# Power.net
KiCad netlist of a schematic drawn in Altium Designer
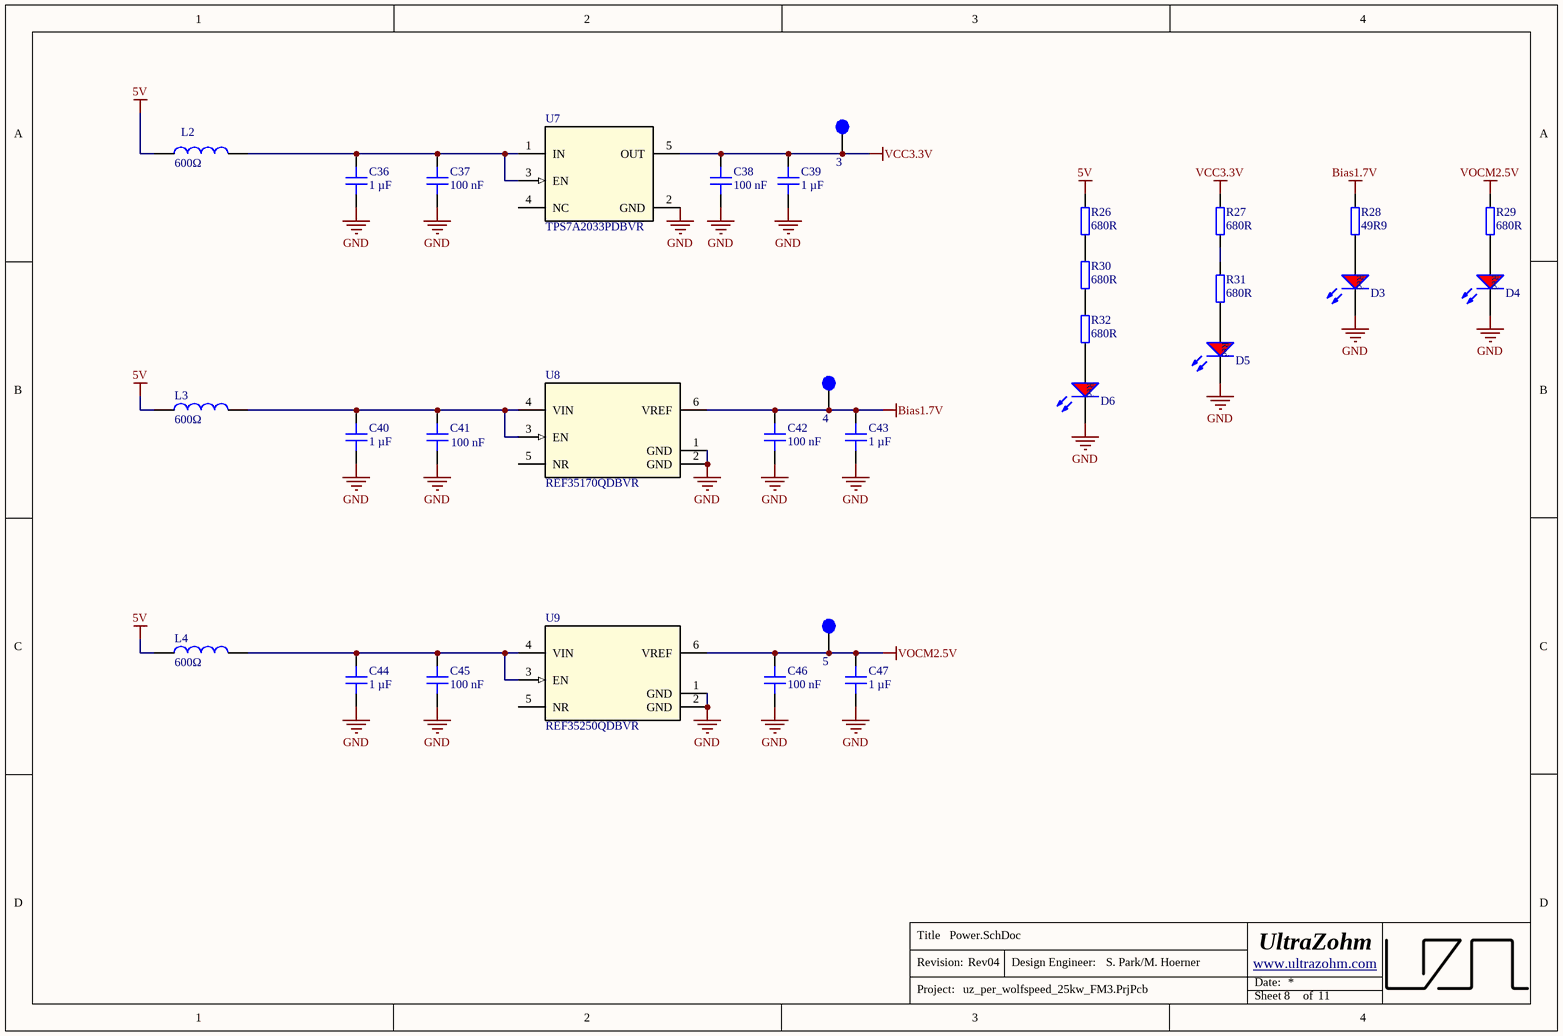
[diagram p0: Power.SchDoc]

(export (version "E")
  (design (tool "Eeschema 10.0.6"))
  (components
    (comp (ref "3")
      (value "Testpoint 1mm")
      (footprint "TP_1mm")
      (fields (field (name "CREATED") "2018_06_25_AGeiger"))
      (libsource (lib "UZOhm_Optical") (part "TP_1mm"))
    )
    (comp (ref "4")
      (value "Testpoint 1mm")
      (footprint "TP_1mm")
      (fields (field (name "CREATED") "2018_06_25_AGeiger"))
      (libsource (lib "UZOhm_Optical") (part "TP_1mm"))
    )
    (comp (ref "5")
      (value "Testpoint 1mm")
      (footprint "TP_1mm")
      (fields (field (name "CREATED") "2018_06_25_AGeiger"))
      (libsource (lib "UZOhm_Optical") (part "TP_1mm"))
    )
    (comp (ref "C36")
      (value "1 µF")
      (footprint "C_0603")
      (description "Capacitor 0603, 25 VDC, 1 µF, X7R")
      (fields
        (field (name "MANUFACTURER PART NUMBER") "C0603C105K3RAC7411")
        (field (name "MANUFACTURER") "KEMET")
        (field (name "CREATED FROM") "MGremer")
      )
      (libsource (lib "user") (part "Capacitor"))
    )
    (comp (ref "C37")
      (value "100 nF")
      (footprint "C_0603")
      (description "Capacitor 0603, 50 VDC, 100nF, X7R")
      (fields
        (field (name "MANUFACTURER PART NUMBER") "C0603C104K5RAC3121")
        (field (name "MANUFACTURER") "KEMET")
        (field (name "CREATED FROM") "DHufnagel")
      )
      (libsource (lib "user") (part "Capacitor"))
    )
    (comp (ref "C38")
      (value "100 nF")
      (footprint "C_0603")
      (description "Capacitor 0603, 50 VDC, 100nF, X7R")
      (fields
        (field (name "MANUFACTURER PART NUMBER") "C0603C104K5RAC3121")
        (field (name "MANUFACTURER") "KEMET")
        (field (name "CREATED FROM") "DHufnagel")
      )
      (libsource (lib "user") (part "Capacitor"))
    )
    (comp (ref "C39")
      (value "1 µF")
      (footprint "C_0603")
      (description "Capacitor 0603, 25 VDC, 1 µF, X7R")
      (fields
        (field (name "MANUFACTURER PART NUMBER") "C0603C105K3RAC7411")
        (field (name "MANUFACTURER") "KEMET")
        (field (name "CREATED FROM") "MGremer")
      )
      (libsource (lib "user") (part "Capacitor"))
    )
    (comp (ref "C40")
      (value "1 µF")
      (footprint "C_0603")
      (description "Capacitor 0603, 25 VDC, 1 µF, X7R")
      (fields
        (field (name "MANUFACTURER PART NUMBER") "C0603C105K3RAC7411")
        (field (name "MANUFACTURER") "KEMET")
        (field (name "CREATED FROM") "MGremer")
      )
      (libsource (lib "user") (part "Capacitor"))
    )
    (comp (ref "C41")
      (value "100 nF")
      (footprint "C_0603")
      (description "Capacitor 0603, 50 VDC, 100nF, X7R")
      (fields
        (field (name "MANUFACTURER PART NUMBER") "C0603C104K5RAC3121")
        (field (name "MANUFACTURER") "KEMET")
        (field (name "CREATED FROM") "DHufnagel")
      )
      (libsource (lib "user") (part "Capacitor"))
    )
    (comp (ref "C42")
      (value "100 nF")
      (footprint "C_0603")
      (description "Capacitor 0603, 50 VDC, 100nF, X7R")
      (fields
        (field (name "MANUFACTURER PART NUMBER") "C0603C104K5RAC3121")
        (field (name "MANUFACTURER") "KEMET")
        (field (name "CREATED FROM") "DHufnagel")
      )
      (libsource (lib "user") (part "Capacitor"))
    )
    (comp (ref "C43")
      (value "1 µF")
      (footprint "C_0603")
      (description "Capacitor 0603, 25 VDC, 1 µF, X7R")
      (fields
        (field (name "MANUFACTURER PART NUMBER") "C0603C105K3RAC7411")
        (field (name "MANUFACTURER") "KEMET")
        (field (name "CREATED FROM") "MGremer")
      )
      (libsource (lib "user") (part "Capacitor"))
    )
    (comp (ref "C44")
      (value "1 µF")
      (footprint "C_0603")
      (description "Capacitor 0603, 25 VDC, 1 µF, X7R")
      (fields
        (field (name "MANUFACTURER PART NUMBER") "C0603C105K3RAC7411")
        (field (name "MANUFACTURER") "KEMET")
        (field (name "CREATED FROM") "MGremer")
      )
      (libsource (lib "user") (part "Capacitor"))
    )
    (comp (ref "C45")
      (value "100 nF")
      (footprint "C_0603")
      (description "Capacitor 0603, 50 VDC, 100nF, X7R")
      (fields
        (field (name "MANUFACTURER PART NUMBER") "C0603C104K5RAC3121")
        (field (name "MANUFACTURER") "KEMET")
        (field (name "CREATED FROM") "DHufnagel")
      )
      (libsource (lib "user") (part "Capacitor"))
    )
    (comp (ref "C46")
      (value "100 nF")
      (footprint "C_0603")
      (description "Capacitor 0603, 50 VDC, 100nF, X7R")
      (fields
        (field (name "MANUFACTURER PART NUMBER") "C0603C104K5RAC3121")
        (field (name "MANUFACTURER") "KEMET")
        (field (name "CREATED FROM") "DHufnagel")
      )
      (libsource (lib "user") (part "Capacitor"))
    )
    (comp (ref "C47")
      (value "1 µF")
      (footprint "C_0603")
      (description "Capacitor 0603, 25 VDC, 1 µF, X7R")
      (fields
        (field (name "MANUFACTURER PART NUMBER") "C0603C105K3RAC7411")
        (field (name "MANUFACTURER") "KEMET")
        (field (name "CREATED FROM") "MGremer")
      )
      (libsource (lib "user") (part "Capacitor"))
    )
    (comp (ref "D3")
      (value "150060RS75000")
      (footprint "WL-SMCW_0603")
      (description "WL-SMCW SMD Mono-color Chip LED Waterclear, size 0603, Red, 2 V, 140°")
      (fields
        (field (name "MF") "Wuerth Elektronik")
        (field (name "LCSC PART NUMBER") "C2286")
        (field (name "CREATED") "2018_09_06_AGeiger")
      )
      (libsource (lib "UZOhm_Optical") (part "LED_Red_0603"))
    )
    (comp (ref "D4")
      (value "150060RS75000")
      (footprint "WL-SMCW_0603")
      (description "WL-SMCW SMD Mono-color Chip LED Waterclear, size 0603, Red, 2 V, 140°")
      (fields
        (field (name "MF") "Wuerth Elektronik")
        (field (name "LCSC PART NUMBER") "C2286")
        (field (name "CREATED") "2018_09_06_AGeiger")
      )
      (libsource (lib "UZOhm_Optical") (part "LED_Red_0603"))
    )
    (comp (ref "D5")
      (value "150060RS75000")
      (footprint "WL-SMCW_0603")
      (description "WL-SMCW SMD Mono-color Chip LED Waterclear, size 0603, Red, 2 V, 140°")
      (fields
        (field (name "MF") "Wuerth Elektronik")
        (field (name "LCSC PART NUMBER") "C2286")
        (field (name "CREATED") "2018_09_06_AGeiger")
      )
      (libsource (lib "UZOhm_Optical") (part "LED_Red_0603"))
    )
    (comp (ref "D6")
      (value "150060RS75000")
      (footprint "WL-SMCW_0603")
      (description "WL-SMCW SMD Mono-color Chip LED Waterclear, size 0603, Red, 2 V, 140°")
      (fields
        (field (name "MF") "Wuerth Elektronik")
        (field (name "LCSC PART NUMBER") "C2286")
        (field (name "CREATED") "2018_09_06_AGeiger")
      )
      (libsource (lib "UZOhm_Optical") (part "LED_Red_0603"))
    )
    (comp (ref "L2")
      (value "600Ω")
      (footprint "WE-CBF_0805_High Current")
      (description "WE-CBF SMD EMI Suppression Ferrite Bead, 0805, 600Ω")
      (fields (field (name "MF") "Wurth Elektronik") (field (name "MPN") "742792040"))
      (libsource (lib "UZOhm_Optical") (part "WE-CBF, 742792040"))
    )
    (comp (ref "L3")
      (value "600Ω")
      (footprint "WE-CBF_0805_High Current")
      (description "WE-CBF SMD EMI Suppression Ferrite Bead, 0805, 600Ω")
      (fields (field (name "MF") "Wurth Elektronik") (field (name "MPN") "742792040"))
      (libsource (lib "UZOhm_Optical") (part "WE-CBF, 742792040"))
    )
    (comp (ref "L4")
      (value "600Ω")
      (footprint "WE-CBF_0805_High Current")
      (description "WE-CBF SMD EMI Suppression Ferrite Bead, 0805, 600Ω")
      (fields (field (name "MF") "Wurth Elektronik") (field (name "MPN") "742792040"))
      (libsource (lib "UZOhm_Optical") (part "WE-CBF, 742792040"))
    )
    (comp (ref "R26")
      (value "680R")
      (footprint "R_0603_N")
      (description "SMD Resistor 0603")
      (fields
        (field (name "TOLERANCE") "1%")
        (field (name "VOLTAGE") "75V")
        (field (name "CREATED") "2018_09_06_AGeiger")
      )
      (libsource (lib "UZOhm_Optical") (part "R_0603"))
    )
    (comp (ref "R27")
      (value "680R")
      (footprint "R_0603_N")
      (description "SMD Resistor 0603")
      (fields
        (field (name "TOLERANCE") "1%")
        (field (name "VOLTAGE") "75V")
        (field (name "CREATED") "2018_09_06_AGeiger")
      )
      (libsource (lib "UZOhm_Optical") (part "R_0603"))
    )
    (comp (ref "R28")
      (value "49R9")
      (footprint "RES 0603_1608")
      (description "SMD resistor 1%")
      (fields
        (field (name "MANUFACTURER PART NUMBER") "RK73H1JTTD49R9F")
        (field (name "MANUFACTURER") "KOA Speer")
        (field (name "CREATED FROM") "DHufnagel")
      )
      (libsource (lib "user") (part "Resistor"))
    )
    (comp (ref "R29")
      (value "680R")
      (footprint "R_0603_N")
      (description "SMD Resistor 0603")
      (fields
        (field (name "TOLERANCE") "1%")
        (field (name "VOLTAGE") "75V")
        (field (name "CREATED") "2018_09_06_AGeiger")
      )
      (libsource (lib "UZOhm_Optical") (part "R_0603"))
    )
    (comp (ref "R30")
      (value "680R")
      (footprint "R_0603_N")
      (description "SMD Resistor 0603")
      (fields
        (field (name "TOLERANCE") "1%")
        (field (name "VOLTAGE") "75V")
        (field (name "CREATED") "2018_09_06_AGeiger")
      )
      (libsource (lib "UZOhm_Optical") (part "R_0603"))
    )
    (comp (ref "R31")
      (value "680R")
      (footprint "R_0603_N")
      (description "SMD Resistor 0603")
      (fields
        (field (name "TOLERANCE") "1%")
        (field (name "VOLTAGE") "75V")
        (field (name "CREATED") "2018_09_06_AGeiger")
      )
      (libsource (lib "UZOhm_Optical") (part "R_0603"))
    )
    (comp (ref "R32")
      (value "680R")
      (footprint "R_0603_N")
      (description "SMD Resistor 0603")
      (fields
        (field (name "TOLERANCE") "1%")
        (field (name "VOLTAGE") "75V")
        (field (name "CREATED") "2018_09_06_AGeiger")
      )
      (libsource (lib "UZOhm_Optical") (part "R_0603"))
    )
    (comp (ref "U7")
      (value "TPS7A2033PDBVR")
      (footprint "DBV0005A-IPC_A")
      (description "No Description Available")
      (fields (field (name "LCSC PART NUMBER") "C2862740"))
      (libsource (lib "TPS7A2033PDBVR") (part "TPS7A2033PDBVR"))
    )
    (comp (ref "U8")
      (value "REF35170QDBVR")
      (footprint "DBV0006A-IPC_A")
      (description "No Description Available")
      (fields (field (name "LCSC PART NUMBER") "C20345634"))
      (libsource (lib "REF35170QDBVR") (part "REF35170QDBVR"))
    )
    (comp (ref "U9")
      (value "REF35250QDBVR")
      (footprint "DBV0006A-IPC_A")
      (description "No Description Available")
      (fields (field (name "LCSC PART NUMBER") "C6265005"))
      (libsource (lib "REF35250QDBVR") (part "REF35250QDBVR"))
    )
  )
  (nets
    (net (code "1") (name "5V") (class "Default")
      (node (ref "L2") (pin "1") (pinfunction "1_1") (pintype "passive"))
      (node (ref "L3") (pin "1") (pinfunction "1_1") (pintype "passive"))
      (node (ref "L4") (pin "1") (pinfunction "1_1") (pintype "passive"))
      (node (ref "R26") (pin "2") (pinfunction "2_2") (pintype "passive"))
    )
    (net (code "2") (name "Bias1.7V") (class "Default")
      (node (ref "4") (pin "1") (pintype "passive"))
      (node (ref "C42") (pin "1") (pinfunction "1_1") (pintype "passive"))
      (node (ref "C43") (pin "1") (pinfunction "1_1") (pintype "passive"))
      (node (ref "R28") (pin "1") (pinfunction "1_1") (pintype "passive"))
      (node (ref "U8") (pin "6") (pinfunction "VREF_6") (pintype "passive"))
    )
    (net (code "3") (name "GND") (class "Default")
      (node (ref "C36") (pin "2") (pinfunction "2_2") (pintype "passive"))
      (node (ref "C37") (pin "2") (pinfunction "2_2") (pintype "passive"))
      (node (ref "C38") (pin "2") (pinfunction "2_2") (pintype "passive"))
      (node (ref "C39") (pin "2") (pinfunction "2_2") (pintype "passive"))
      (node (ref "C40") (pin "2") (pinfunction "2_2") (pintype "passive"))
      (node (ref "C41") (pin "2") (pinfunction "2_2") (pintype "passive"))
      (node (ref "C42") (pin "2") (pinfunction "2_2") (pintype "passive"))
      (node (ref "C43") (pin "2") (pinfunction "2_2") (pintype "passive"))
      (node (ref "C44") (pin "2") (pinfunction "2_2") (pintype "passive"))
      (node (ref "C45") (pin "2") (pinfunction "2_2") (pintype "passive"))
      (node (ref "C46") (pin "2") (pinfunction "2_2") (pintype "passive"))
      (node (ref "C47") (pin "2") (pinfunction "2_2") (pintype "passive"))
      (node (ref "D3") (pin "1") (pinfunction "K_1") (pintype "passive"))
      (node (ref "D4") (pin "1") (pinfunction "K_1") (pintype "passive"))
      (node (ref "D5") (pin "1") (pinfunction "K_1") (pintype "passive"))
      (node (ref "D6") (pin "1") (pinfunction "K_1") (pintype "passive"))
      (node (ref "U7") (pin "2") (pinfunction "GND_2") (pintype "power_in"))
      (node (ref "U8") (pin "1") (pinfunction "GND_1") (pintype "power_in"))
      (node (ref "U8") (pin "2") (pinfunction "GND_2") (pintype "power_in"))
      (node (ref "U9") (pin "1") (pinfunction "GND_1") (pintype "power_in"))
      (node (ref "U9") (pin "2") (pinfunction "GND_2") (pintype "power_in"))
    )
    (net (code "4") (name "Net-(D3-A)") (class "Default")
      (node (ref "D3") (pin "2") (pinfunction "A_2") (pintype "passive"))
      (node (ref "R28") (pin "2") (pinfunction "2_2") (pintype "passive"))
    )
    (net (code "5") (name "Net-(D4-A)") (class "Default")
      (node (ref "D4") (pin "2") (pinfunction "A_2") (pintype "passive"))
      (node (ref "R29") (pin "1") (pinfunction "1_1") (pintype "passive"))
    )
    (net (code "6") (name "Net-(D5-A)") (class "Default")
      (node (ref "D5") (pin "2") (pinfunction "A_2") (pintype "passive"))
      (node (ref "R31") (pin "1") (pinfunction "1_1") (pintype "passive"))
    )
    (net (code "7") (name "Net-(D6-A)") (class "Default")
      (node (ref "D6") (pin "2") (pinfunction "A_2") (pintype "passive"))
      (node (ref "R32") (pin "1") (pinfunction "1_1") (pintype "passive"))
    )
    (net (code "8") (name "Net-(R26-Pad1)") (class "Default")
      (node (ref "R26") (pin "1") (pinfunction "1_1") (pintype "passive"))
      (node (ref "R30") (pin "2") (pinfunction "2_2") (pintype "passive"))
    )
    (net (code "9") (name "Net-(R27-Pad1)") (class "Default")
      (node (ref "R27") (pin "1") (pinfunction "1_1") (pintype "passive"))
      (node (ref "R31") (pin "2") (pinfunction "2_2") (pintype "passive"))
    )
    (net (code "10") (name "Net-(R30-Pad1)") (class "Default")
      (node (ref "R30") (pin "1") (pinfunction "1_1") (pintype "passive"))
      (node (ref "R32") (pin "2") (pinfunction "2_2") (pintype "passive"))
    )
    (net (code "11") (name "Net-(U7-EN)") (class "Default")
      (node (ref "C36") (pin "1") (pinfunction "1_1") (pintype "passive"))
      (node (ref "C37") (pin "1") (pinfunction "1_1") (pintype "passive"))
      (node (ref "L2") (pin "2") (pinfunction "2_2") (pintype "passive"))
      (node (ref "U7") (pin "1") (pinfunction "IN_1") (pintype "power_in"))
      (node (ref "U7") (pin "3") (pinfunction "EN_3") (pintype "input"))
    )
    (net (code "12") (name "Net-(U8-EN)") (class "Default")
      (node (ref "C40") (pin "1") (pinfunction "1_1") (pintype "passive"))
      (node (ref "C41") (pin "1") (pinfunction "1_1") (pintype "passive"))
      (node (ref "L3") (pin "2") (pinfunction "2_2") (pintype "passive"))
      (node (ref "U8") (pin "3") (pinfunction "EN_3") (pintype "input"))
      (node (ref "U8") (pin "4") (pinfunction "VIN_4") (pintype "power_in"))
    )
    (net (code "13") (name "Net-(U9-EN)") (class "Default")
      (node (ref "C44") (pin "1") (pinfunction "1_1") (pintype "passive"))
      (node (ref "C45") (pin "1") (pinfunction "1_1") (pintype "passive"))
      (node (ref "L4") (pin "2") (pinfunction "2_2") (pintype "passive"))
      (node (ref "U9") (pin "3") (pinfunction "EN_3") (pintype "input"))
      (node (ref "U9") (pin "4") (pinfunction "VIN_4") (pintype "power_in"))
    )
    (net (code "14") (name "VCC3.3V") (class "Default")
      (node (ref "3") (pin "1") (pintype "passive"))
      (node (ref "C38") (pin "1") (pinfunction "1_1") (pintype "passive"))
      (node (ref "C39") (pin "1") (pinfunction "1_1") (pintype "passive"))
      (node (ref "R27") (pin "2") (pinfunction "2_2") (pintype "passive"))
      (node (ref "U7") (pin "5") (pinfunction "OUT_5") (pintype "passive"))
    )
    (net (code "15") (name "VOCM2.5V") (class "Default")
      (node (ref "5") (pin "1") (pintype "passive"))
      (node (ref "C46") (pin "1") (pinfunction "1_1") (pintype "passive"))
      (node (ref "C47") (pin "1") (pinfunction "1_1") (pintype "passive"))
      (node (ref "R29") (pin "2") (pinfunction "2_2") (pintype "passive"))
      (node (ref "U9") (pin "6") (pinfunction "VREF_6") (pintype "passive"))
    )
    (net (code "16") (name "unconnected-(U7-NC-Pad4)") (class "Default")
      (node (ref "U7") (pin "4") (pinfunction "NC_4") (pintype "passive"))
    )
    (net (code "17") (name "unconnected-(U8-NR-Pad5)") (class "Default")
      (node (ref "U8") (pin "5") (pinfunction "NR_5") (pintype "passive"))
    )
    (net (code "18") (name "unconnected-(U9-NR-Pad5)") (class "Default")
      (node (ref "U9") (pin "5") (pinfunction "NR_5") (pintype "passive"))
    )
  )
)
